# shd_v2_1.net
KiCad netlist of a schematic drawn in EAGLE
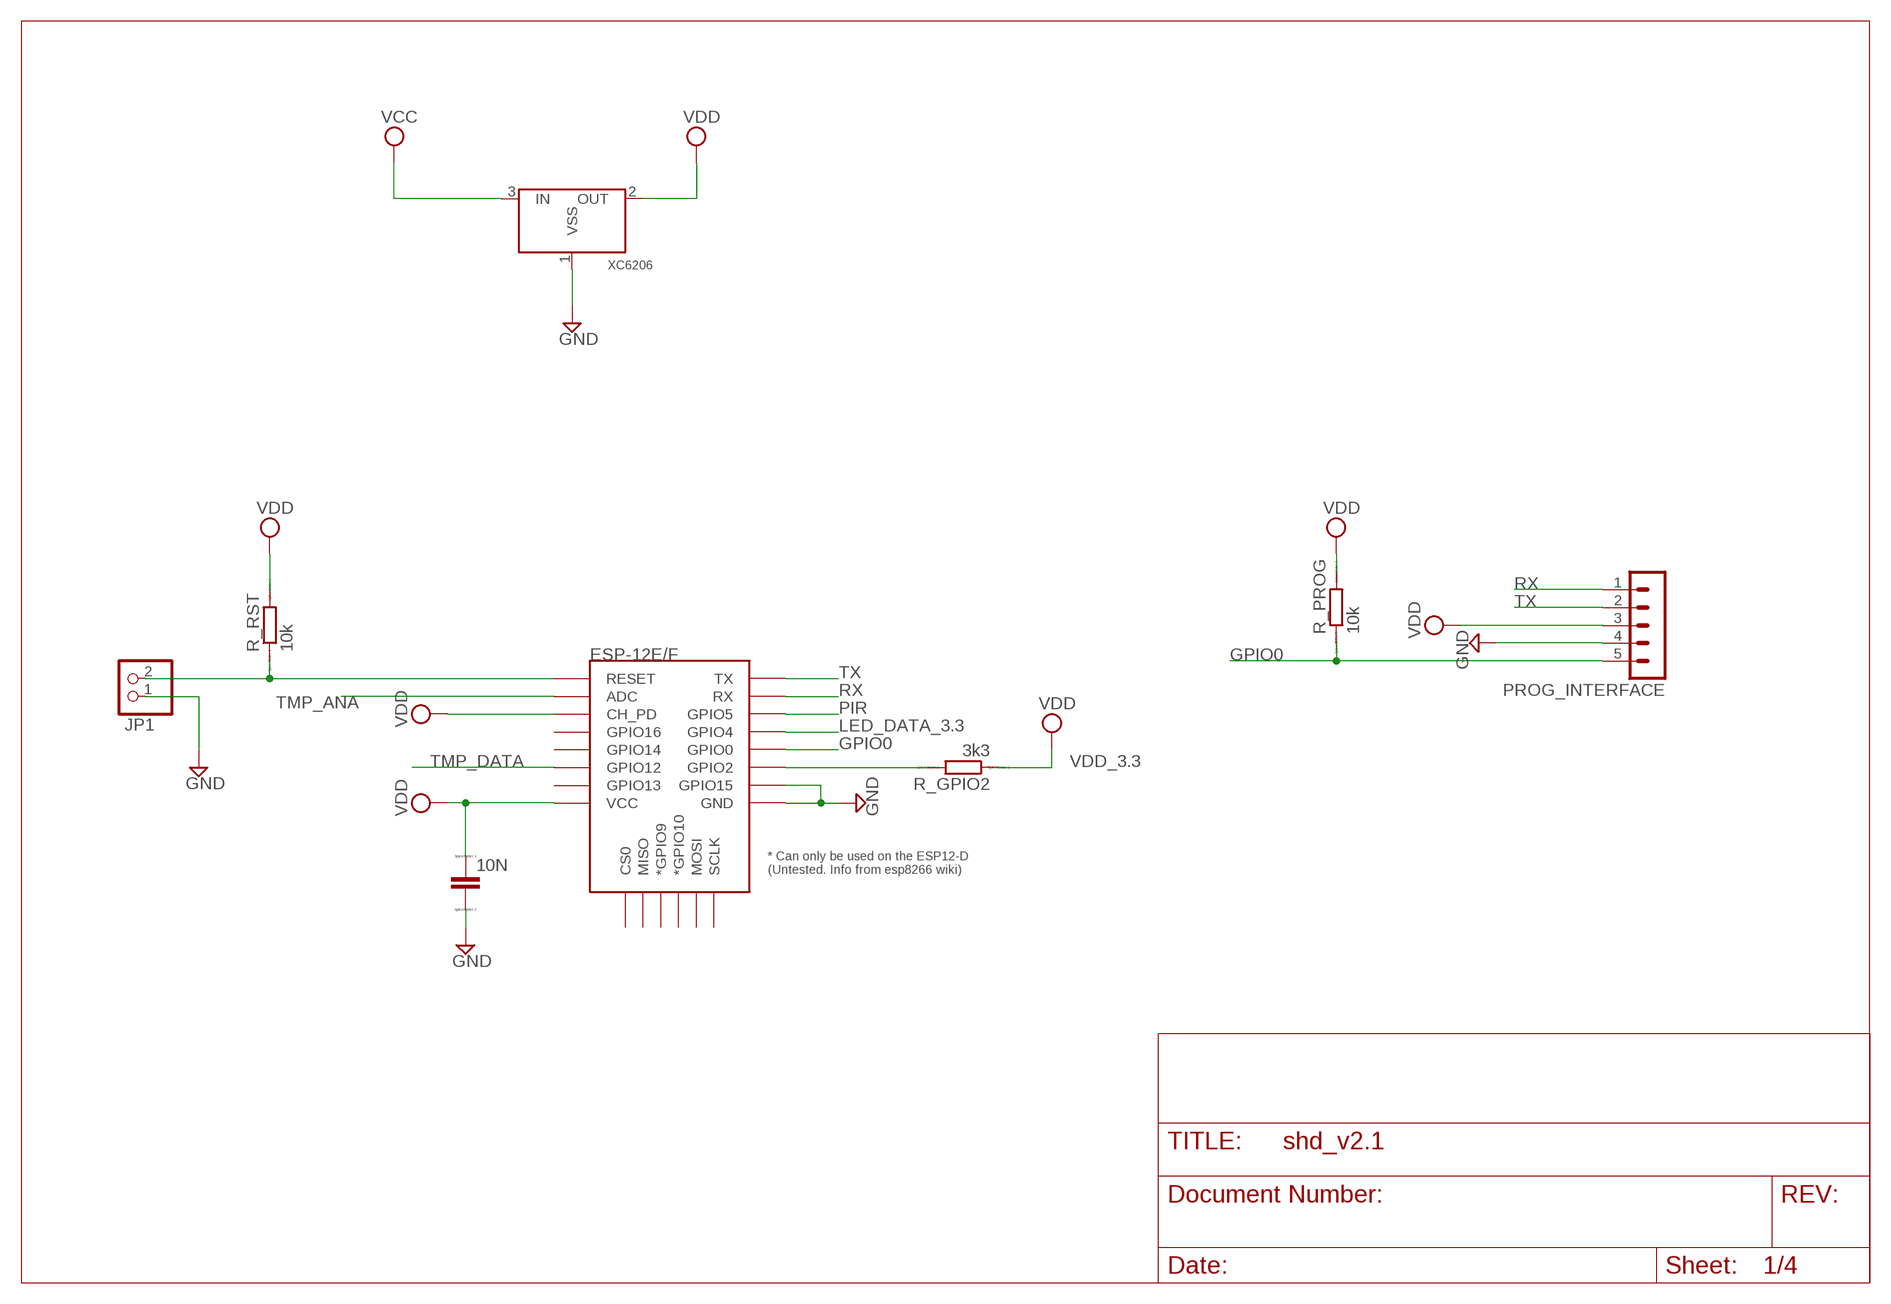
[diagram p0: schematic, sheet 1]
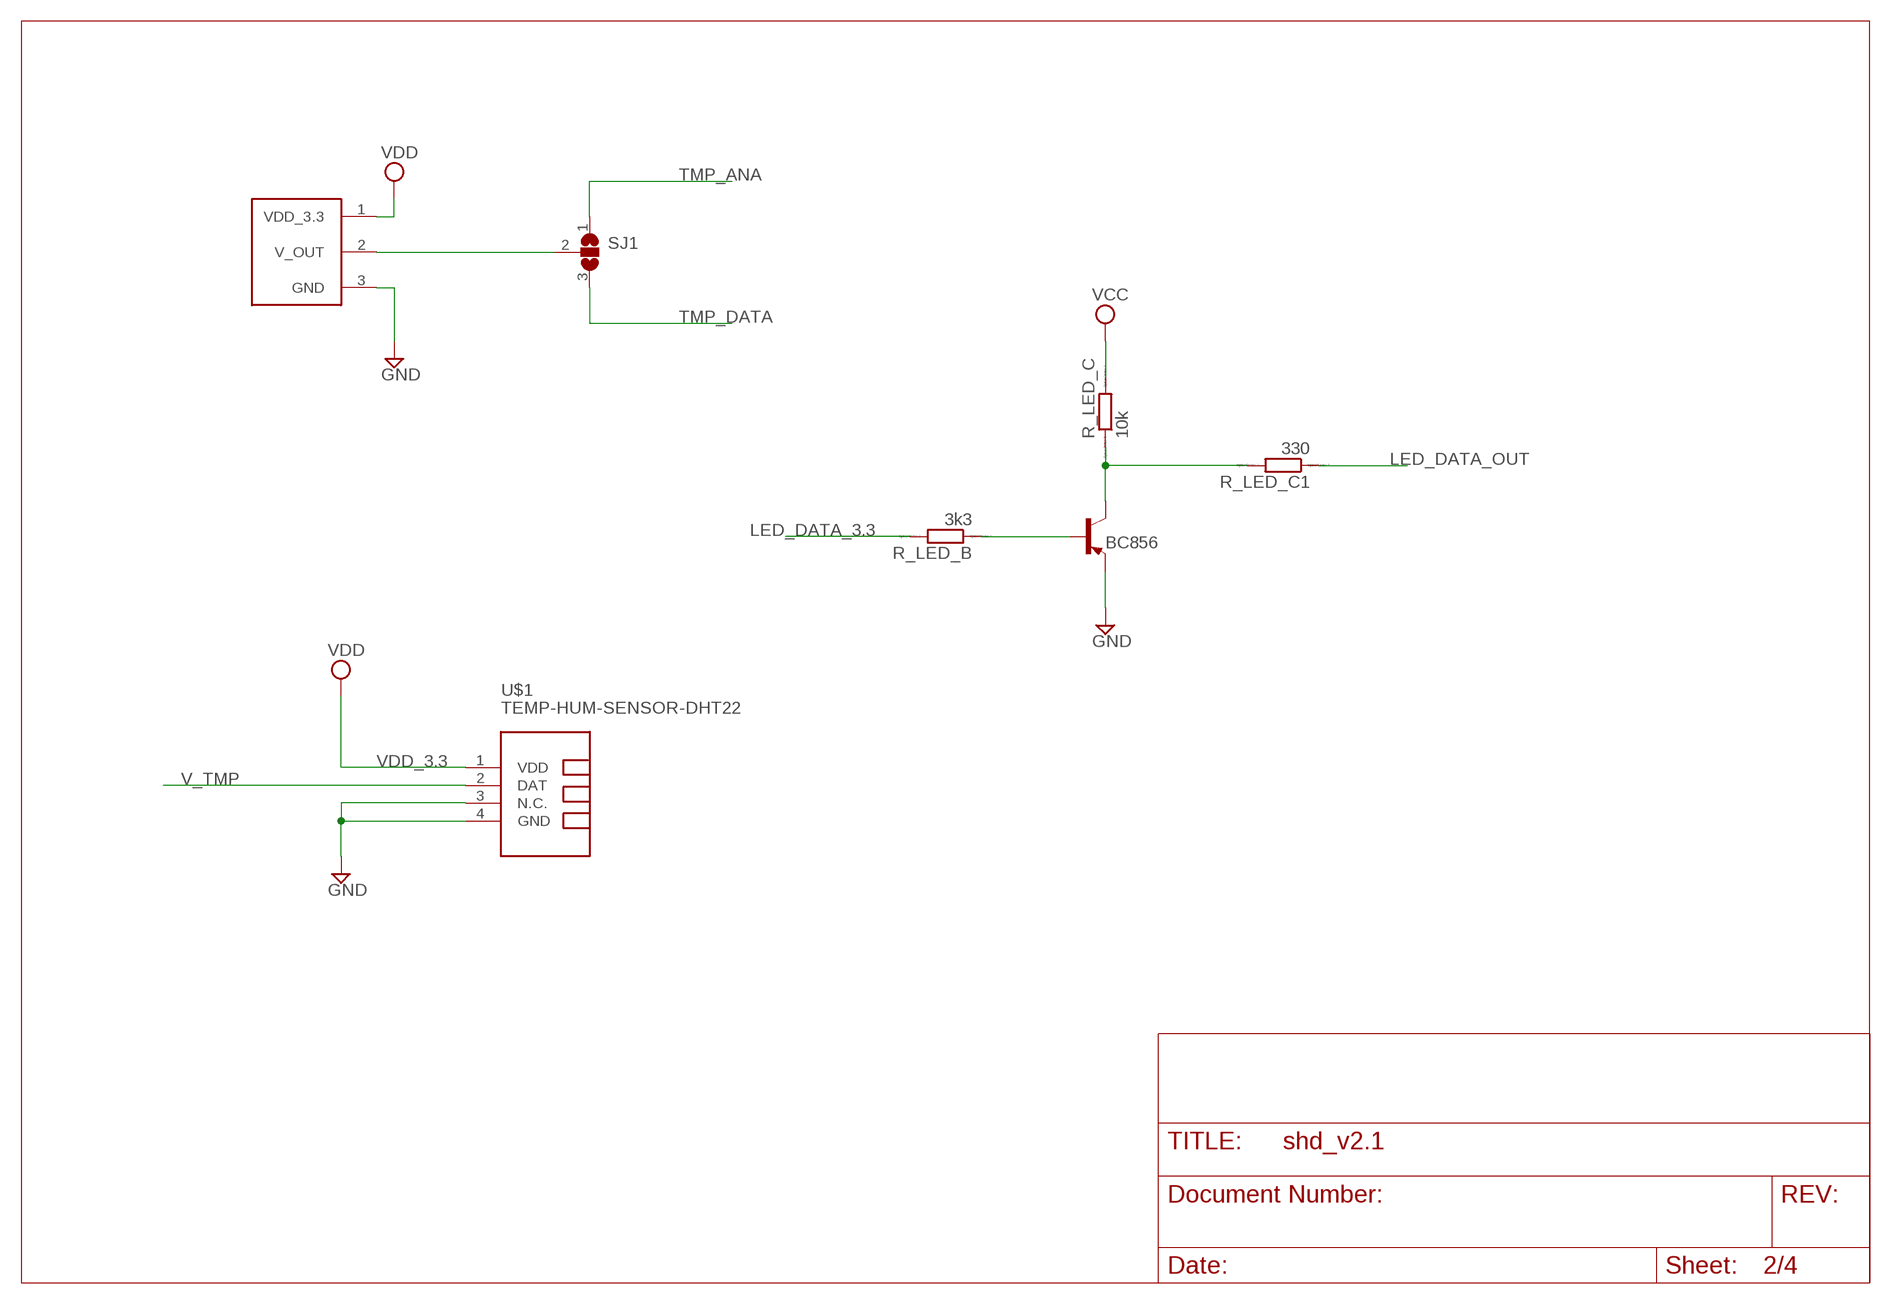
[diagram p1: schematic, sheet 2]
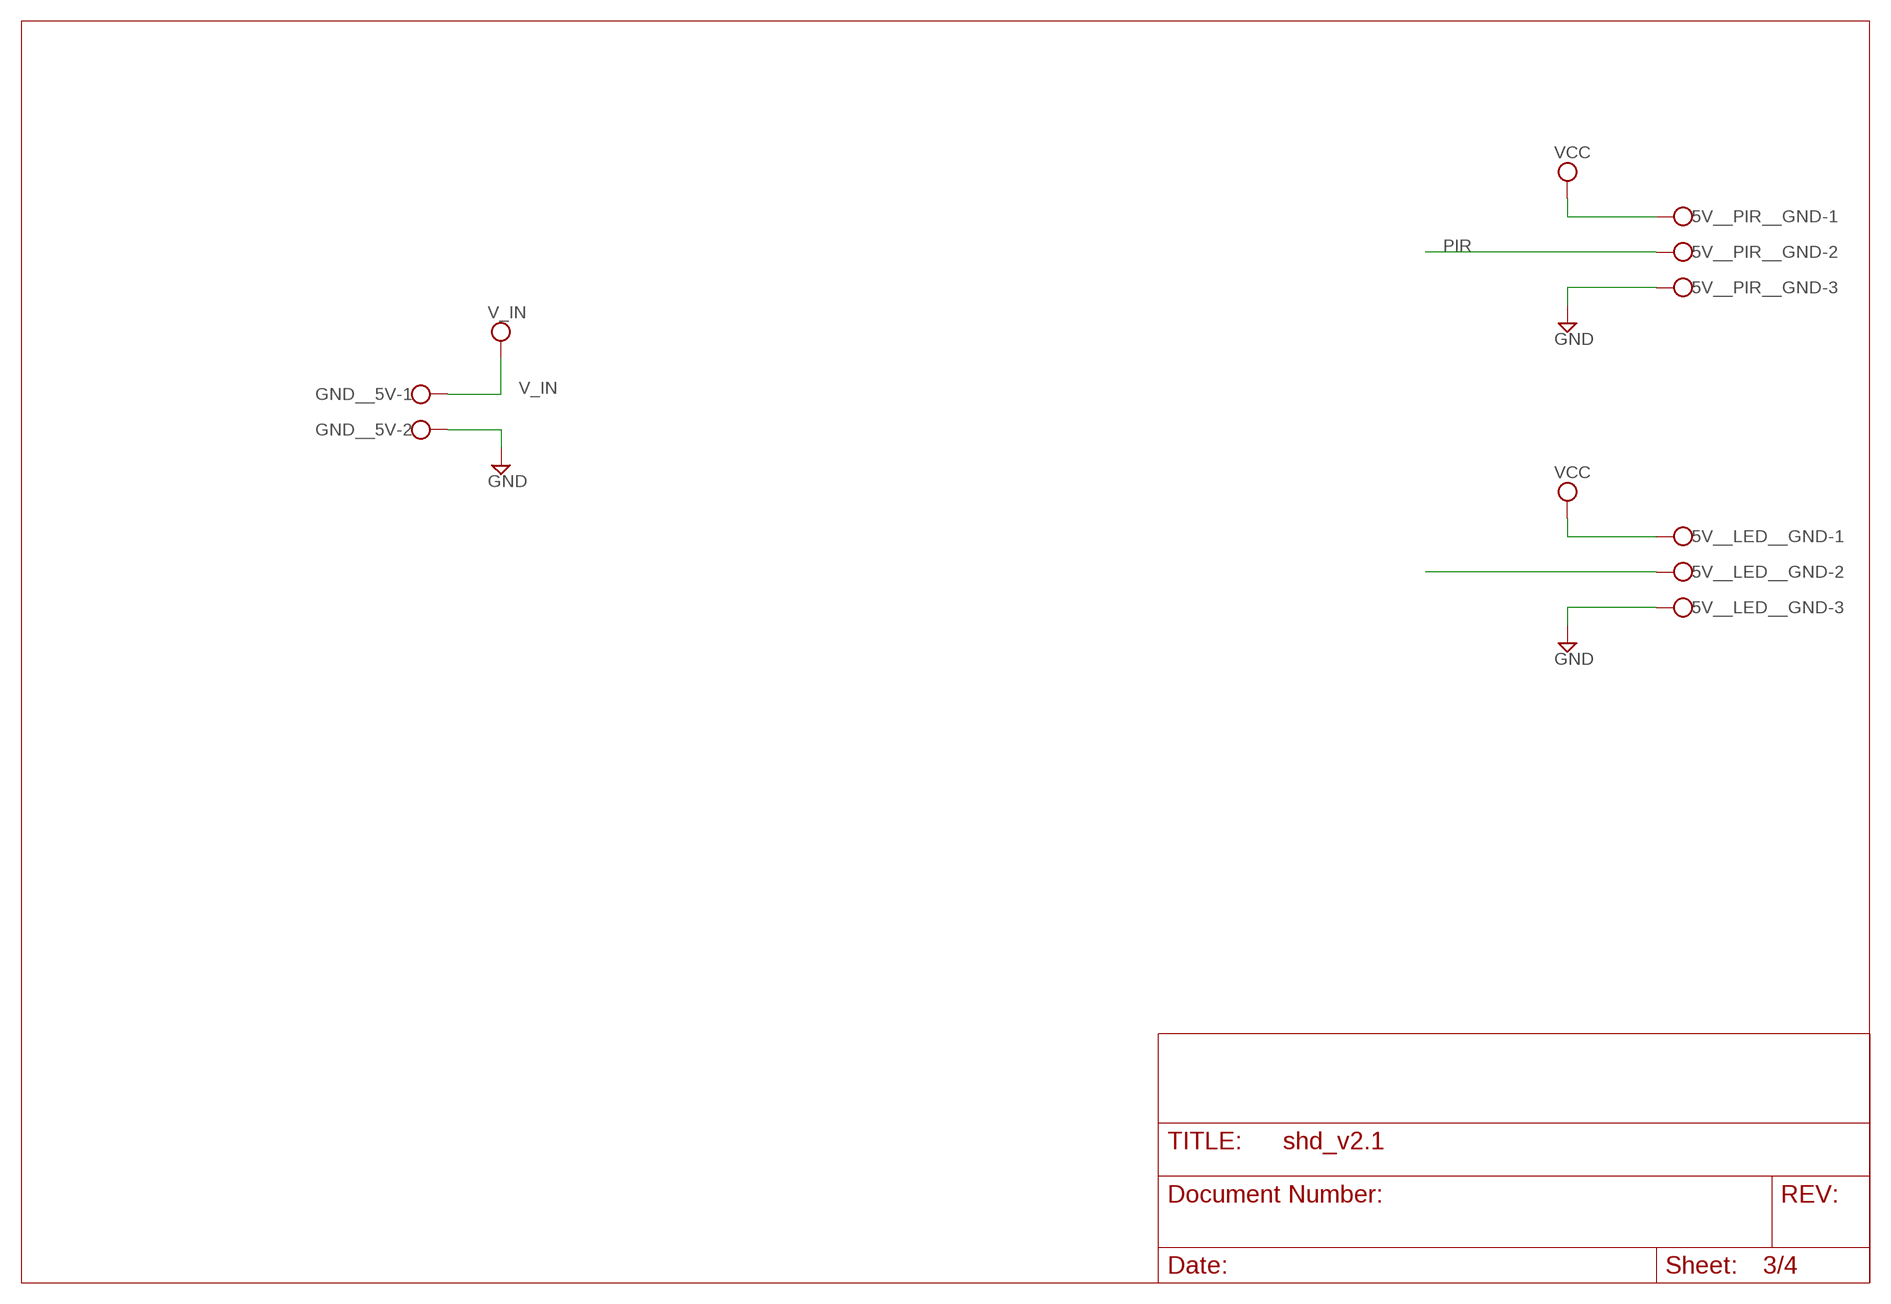
[diagram p2: schematic, sheet 3]
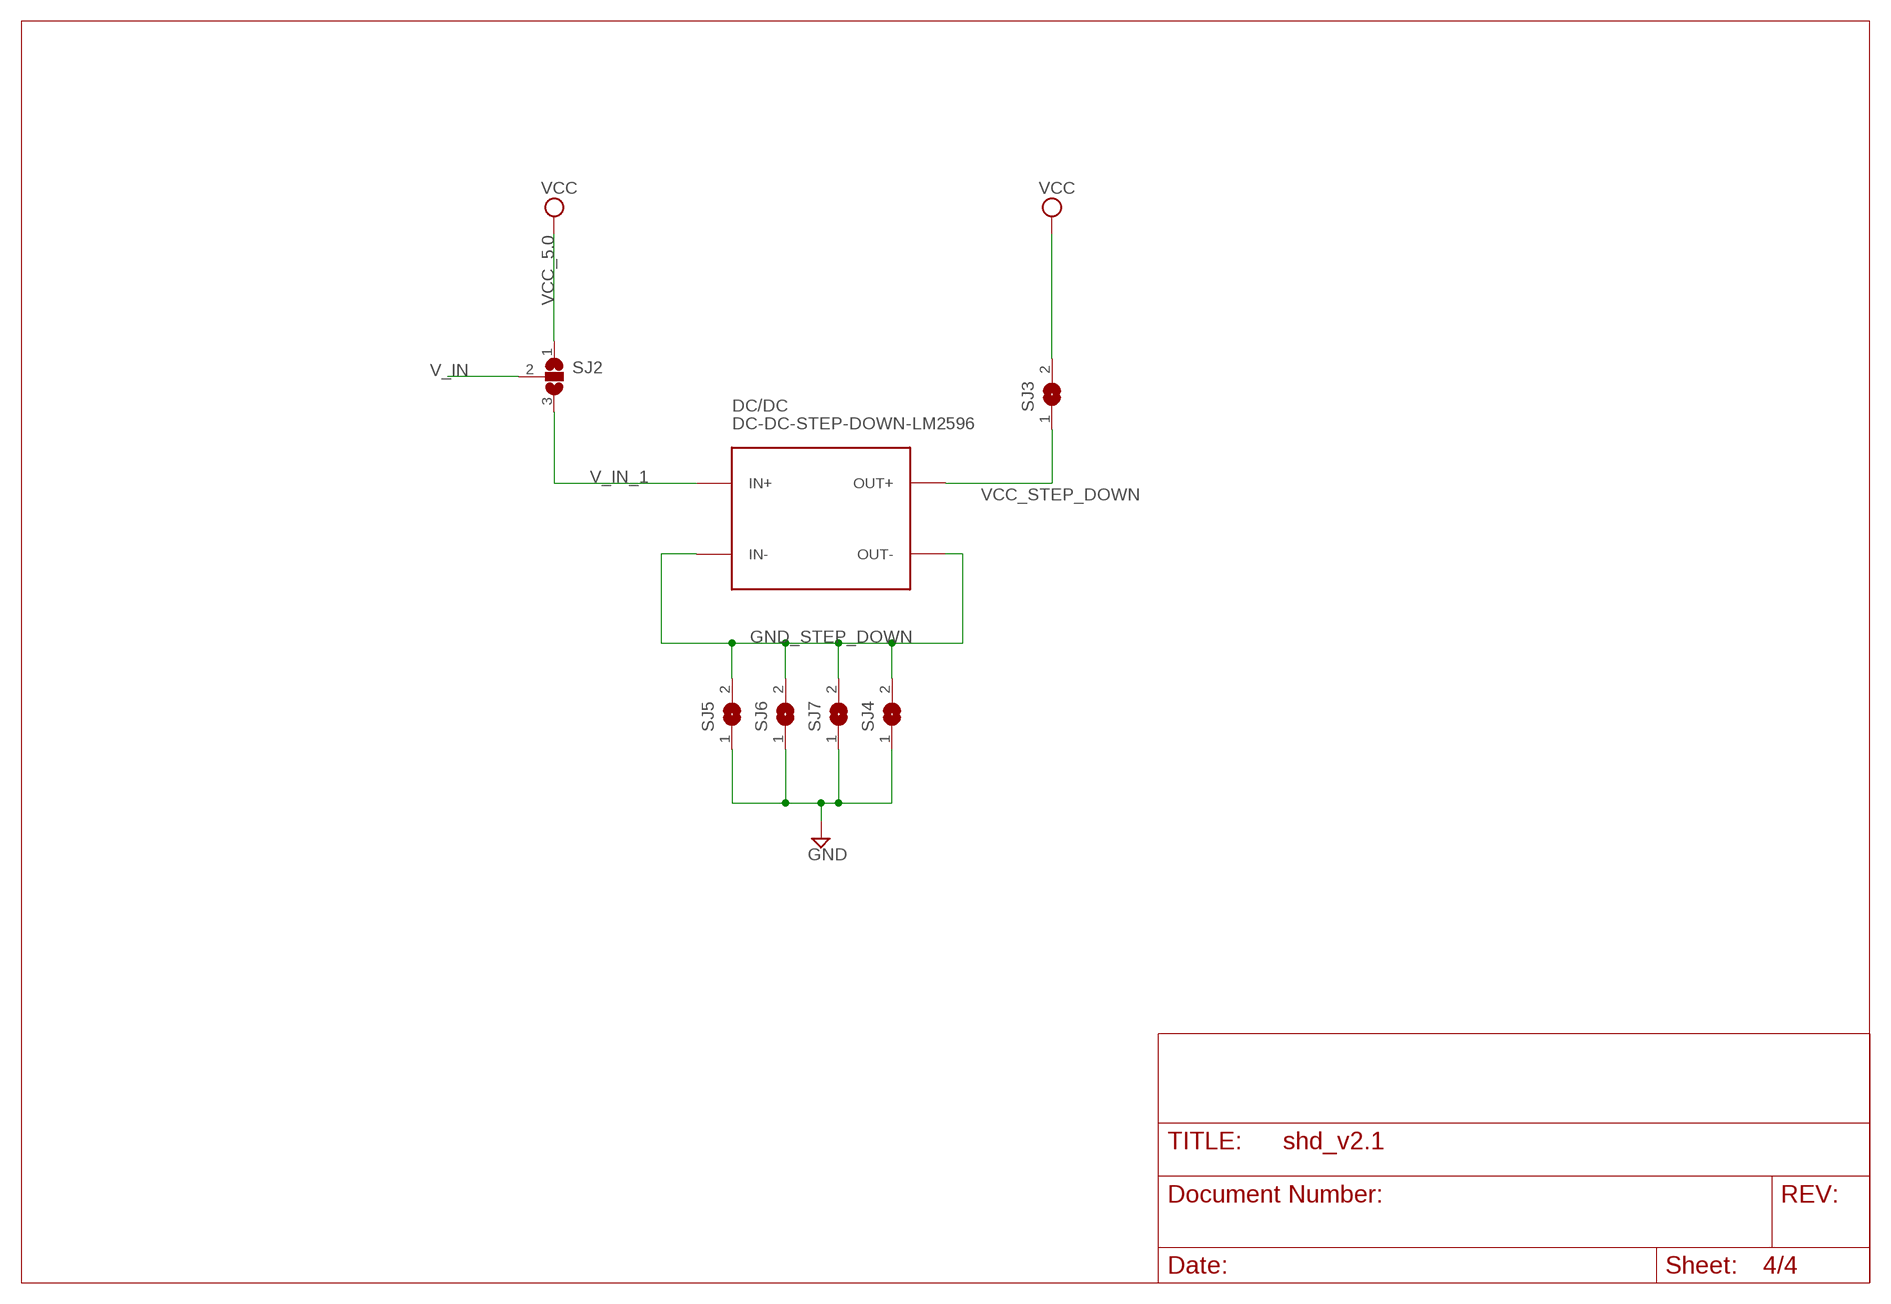
[diagram p3: schematic, sheet 4]

(export (version "E")
  (design (tool "Eeschema 10.0.6"))
  (components
    (comp (ref "DC/DC")
      (value "DC-DC-STEP-DOWN-LM2596")
      (footprint "eagle-import:DC-DC-STEP-DOWN-LM2596")
      (libsource (lib "eagle-import") (part "DC-DC-STEP-DOWN-LM2596"))
    )
    (comp (ref "SJ2")
      (value "SJ2W")
      (footprint "eagle-import:SJ_2")
      (libsource (lib "eagle-import") (part "SJ2W"))
    )
    (comp (ref "SJ3") (value "SJ") (footprint "eagle-import:SJ") (libsource (lib "eagle-import") (part "SJ")))
    (comp (ref "SJ4") (value "SJ") (footprint "eagle-import:SJ") (libsource (lib "eagle-import") (part "SJ")))
    (comp (ref "SJ5") (value "SJ") (footprint "eagle-import:SJ") (libsource (lib "eagle-import") (part "SJ")))
    (comp (ref "SJ6") (value "SJ") (footprint "eagle-import:SJ") (libsource (lib "eagle-import") (part "SJ")))
    (comp (ref "SJ7") (value "SJ") (footprint "eagle-import:SJ") (libsource (lib "eagle-import") (part "SJ")))
    (comp (ref "10N")
      (value "C")
      (footprint "eagle-import:C0805")
      (libsource (lib "eagle-import") (part "C"))
    )
    (comp (ref "ESP-12E/F")
      (value "ESP12ESMD")
      (footprint "eagle-import:ESP12E-SMD")
      (libsource (lib "eagle-import") (part "ESP12ESMD"))
    )
    (comp (ref "JP1")
      (value "PINHD-1X2")
      (footprint "eagle-import:1X02")
      (libsource (lib "eagle-import") (part "PINHD-1X2"))
    )
    (comp (ref "PROG_INTERFACE")
      (value "MA05-1")
      (footprint "eagle-import:MA05-1")
      (libsource (lib "eagle-import") (part "MA05-1"))
    )
    (comp (ref "R_GPIO2")
      (value "3k3")
      (footprint "eagle-import:0207_10")
      (libsource (lib "eagle-import") (part "R0207/10"))
    )
    (comp (ref "R_PROG")
      (value "10k")
      (footprint "eagle-import:0207_10")
      (libsource (lib "eagle-import") (part "R0207/10"))
    )
    (comp (ref "R_RST")
      (value "10k")
      (footprint "eagle-import:0207_10")
      (libsource (lib "eagle-import") (part "R0207/10"))
    )
    (comp (ref "XC6206")
      (value "XC6206")
      (footprint "eagle-import:SOT23")
      (libsource (lib "eagle-import") (part "XC6206"))
    )
    (comp (ref "BC856")
      (value "BC856A-PNP-SOT23-BEC")
      (footprint "eagle-import:SOT23-BEC")
      (libsource (lib "eagle-import") (part "-PNP-SOT23-BECBC856A"))
    )
    (comp (ref "R_LED_B")
      (value "3k3")
      (footprint "eagle-import:0207_10")
      (libsource (lib "eagle-import") (part "R0207/10"))
    )
    (comp (ref "R_LED_C")
      (value "10k")
      (footprint "eagle-import:0207_10")
      (libsource (lib "eagle-import") (part "R0207/10"))
    )
    (comp (ref "R_LED_C1")
      (value "330")
      (footprint "eagle-import:0207_10")
      (libsource (lib "eagle-import") (part "R0207/10"))
    )
    (comp (ref "SJ1")
      (value "SJ2W")
      (footprint "eagle-import:SJ_2")
      (libsource (lib "eagle-import") (part "SJ2W"))
    )
    (comp (ref "TMP")
      (value "TMP36")
      (footprint "eagle-import:TO-92")
      (libsource (lib "eagle-import") (part "TMP36"))
    )
    (comp (ref "U$1")
      (value "TEMP-HUM-SENSOR-DHT22")
      (footprint "eagle-import:TEMP-HUM-SENSOR-DHT22")
      (libsource (lib "eagle-import") (part "TEMP-HUM-SENSOR-DHT22"))
    )
    (comp (ref "5V__LED__GND")
      (value "W237-103")
      (footprint "eagle-import:W237-103")
      (fields (field (name "MPN") "237-103"))
      (libsource (lib "eagle-import") (part "W237-103"))
    )
    (comp (ref "5V__PIR__GND")
      (value "W237-103")
      (footprint "eagle-import:W237-103")
      (fields (field (name "MPN") "237-103"))
      (libsource (lib "eagle-import") (part "W237-103"))
    )
    (comp (ref "GND__5V")
      (value "W237-102")
      (footprint "eagle-import:W237-102")
      (fields (field (name "MPN") "237-102"))
      (libsource (lib "eagle-import") (part "W237-102"))
    )
  )
  (nets
    (net (code "1") (name "GND") (class "Default")
      (node (ref "10N") (pin "2") (pinfunction "2_2") (pintype "passive"))
      (node (ref "5V__LED__GND") (pin "3") (pinfunction "KL_3") (pintype "passive"))
      (node (ref "5V__PIR__GND") (pin "3") (pinfunction "KL_3") (pintype "passive"))
      (node (ref "BC856") (pin "E") (pinfunction "E_E") (pintype "passive"))
      (node (ref "ESP-12E/F") (pin "GND") (pinfunction "GND_GND") (pintype "bidirectional"))
      (node (ref "ESP-12E/F") (pin "GPIO15") (pinfunction "GPIO15_GPIO15") (pintype "bidirectional"))
      (node (ref "GND__5V") (pin "2") (pinfunction "KL_2") (pintype "passive"))
      (node (ref "JP1") (pin "1") (pinfunction "1_1") (pintype "passive"))
      (node (ref "PROG_INTERFACE") (pin "4") (pinfunction "4_4") (pintype "passive"))
      (node (ref "SJ4") (pin "1") (pinfunction "1_1") (pintype "passive"))
      (node (ref "SJ5") (pin "1") (pinfunction "1_1") (pintype "passive"))
      (node (ref "SJ6") (pin "1") (pinfunction "1_1") (pintype "passive"))
      (node (ref "SJ7") (pin "1") (pinfunction "1_1") (pintype "passive"))
      (node (ref "TMP") (pin "3") (pinfunction "GND_3") (pintype "power_in"))
      (node (ref "U$1") (pin "3") (pinfunction "N.C._3") (pintype "passive"))
      (node (ref "U$1") (pin "4") (pinfunction "GND_4") (pintype "power_in"))
      (node (ref "XC6206") (pin "1") (pinfunction "VSS_1") (pintype "bidirectional"))
    )
    (net (code "2") (name "GND_STEP_DOWN") (class "Default")
      (node (ref "DC/DC") (pin "IN-") (pinfunction "IN-_IN-") (pintype "bidirectional"))
      (node (ref "DC/DC") (pin "OUT-") (pinfunction "OUT-_OUT-") (pintype "bidirectional"))
      (node (ref "SJ4") (pin "2") (pinfunction "2_2") (pintype "passive"))
      (node (ref "SJ5") (pin "2") (pinfunction "2_2") (pintype "passive"))
      (node (ref "SJ6") (pin "2") (pinfunction "2_2") (pintype "passive"))
      (node (ref "SJ7") (pin "2") (pinfunction "2_2") (pintype "passive"))
    )
    (net (code "3") (name "GPIO0") (class "Default")
      (node (ref "ESP-12E/F") (pin "GPIO0") (pinfunction "GPIO0_GPIO0") (pintype "bidirectional"))
      (node (ref "PROG_INTERFACE") (pin "5") (pinfunction "5_5") (pintype "passive"))
      (node (ref "R_PROG") (pin "1") (pinfunction "1_1") (pintype "passive"))
    )
    (net (code "4") (name "LED_DATA_3.3") (class "Default")
      (node (ref "ESP-12E/F") (pin "GPIO4") (pinfunction "GPIO4_GPIO4") (pintype "bidirectional"))
      (node (ref "R_LED_B") (pin "2") (pinfunction "2_2") (pintype "passive"))
    )
    (net (code "5") (name "LED_DATA_OUT") (class "Default")
      (node (ref "5V__LED__GND") (pin "2") (pinfunction "KL_2") (pintype "passive"))
      (node (ref "R_LED_C1") (pin "1") (pinfunction "1_1") (pintype "passive"))
    )
    (net (code "6") (name "Net-(BC856-PadB)") (class "Default")
      (node (ref "BC856") (pin "B") (pinfunction "B_B") (pintype "passive"))
      (node (ref "R_LED_B") (pin "1") (pinfunction "1_1") (pintype "passive"))
    )
    (net (code "7") (name "Net-(BC856-PadC)") (class "Default")
      (node (ref "BC856") (pin "C") (pinfunction "C_C") (pintype "passive"))
      (node (ref "R_LED_C") (pin "1") (pinfunction "1_1") (pintype "passive"))
      (node (ref "R_LED_C1") (pin "2") (pinfunction "2_2") (pintype "passive"))
    )
    (net (code "8") (name "Net-(ESP-12E/F-PadGPIO2)") (class "Default")
      (node (ref "ESP-12E/F") (pin "GPIO2") (pinfunction "GPIO2_GPIO2") (pintype "bidirectional"))
      (node (ref "R_GPIO2") (pin "2") (pinfunction "2_2") (pintype "passive"))
    )
    (net (code "9") (name "Net-(ESP-12E/F-PadRESET)") (class "Default")
      (node (ref "ESP-12E/F") (pin "RESET") (pinfunction "RESET_RESET") (pintype "bidirectional"))
      (node (ref "JP1") (pin "2") (pinfunction "2_2") (pintype "passive"))
      (node (ref "R_RST") (pin "1") (pinfunction "1_1") (pintype "passive"))
    )
    (net (code "10") (name "PIR") (class "Default")
      (node (ref "5V__PIR__GND") (pin "2") (pinfunction "KL_2") (pintype "passive"))
      (node (ref "ESP-12E/F") (pin "GPIO5") (pinfunction "GPIO5_GPIO5") (pintype "bidirectional"))
    )
    (net (code "11") (name "RX") (class "Default")
      (node (ref "ESP-12E/F") (pin "RXD0") (pinfunction "RX_RXD0") (pintype "bidirectional"))
      (node (ref "PROG_INTERFACE") (pin "1") (pinfunction "1_1") (pintype "passive"))
    )
    (net (code "12") (name "TMP_ANA") (class "Default")
      (node (ref "ESP-12E/F") (pin "ADC") (pinfunction "ADC_ADC") (pintype "bidirectional"))
      (node (ref "SJ1") (pin "1") (pinfunction "1_1") (pintype "passive"))
    )
    (net (code "13") (name "TMP_DATA") (class "Default")
      (node (ref "ESP-12E/F") (pin "GPIO12") (pinfunction "GPIO12_GPIO12") (pintype "bidirectional"))
      (node (ref "SJ1") (pin "3") (pinfunction "3_3") (pintype "passive"))
    )
    (net (code "14") (name "TX") (class "Default")
      (node (ref "ESP-12E/F") (pin "TXD0") (pinfunction "TX_TXD0") (pintype "bidirectional"))
      (node (ref "PROG_INTERFACE") (pin "2") (pinfunction "2_2") (pintype "passive"))
    )
    (net (code "15") (name "VCC_5.0") (class "Default")
      (node (ref "5V__LED__GND") (pin "1") (pinfunction "KL_1") (pintype "passive"))
      (node (ref "5V__PIR__GND") (pin "1") (pinfunction "KL_1") (pintype "passive"))
      (node (ref "R_LED_C") (pin "2") (pinfunction "2_2") (pintype "passive"))
      (node (ref "SJ2") (pin "1") (pinfunction "1_1") (pintype "passive"))
      (node (ref "SJ3") (pin "2") (pinfunction "2_2") (pintype "passive"))
      (node (ref "XC6206") (pin "3") (pinfunction "IN_3") (pintype "bidirectional"))
    )
    (net (code "16") (name "VCC_STEP_DOWN") (class "Default")
      (node (ref "DC/DC") (pin "OUT+") (pinfunction "OUT+_OUT+") (pintype "bidirectional"))
      (node (ref "SJ3") (pin "1") (pinfunction "1_1") (pintype "passive"))
    )
    (net (code "17") (name "VDD_3.3") (class "Default")
      (node (ref "10N") (pin "1") (pinfunction "1_1") (pintype "passive"))
      (node (ref "ESP-12E/F") (pin "CH_PD") (pinfunction "CH_PD_CH_PD") (pintype "bidirectional"))
      (node (ref "ESP-12E/F") (pin "VCC") (pinfunction "VCC_VCC") (pintype "bidirectional"))
      (node (ref "PROG_INTERFACE") (pin "3") (pinfunction "3_3") (pintype "passive"))
      (node (ref "R_GPIO2") (pin "1") (pinfunction "1_1") (pintype "passive"))
      (node (ref "R_PROG") (pin "2") (pinfunction "2_2") (pintype "passive"))
      (node (ref "R_RST") (pin "2") (pinfunction "2_2") (pintype "passive"))
      (node (ref "TMP") (pin "1") (pinfunction "VDD_3.3_1") (pintype "power_in"))
      (node (ref "U$1") (pin "1") (pinfunction "VDD_1") (pintype "power_in"))
      (node (ref "XC6206") (pin "2") (pinfunction "OUT_2") (pintype "bidirectional"))
    )
    (net (code "18") (name "V_IN") (class "Default")
      (node (ref "GND__5V") (pin "1") (pinfunction "KL_1") (pintype "passive"))
      (node (ref "SJ2") (pin "2") (pinfunction "2_2") (pintype "passive"))
    )
    (net (code "19") (name "V_IN_1") (class "Default")
      (node (ref "DC/DC") (pin "IN+") (pinfunction "IN+_IN+") (pintype "bidirectional"))
      (node (ref "SJ2") (pin "3") (pinfunction "3_3") (pintype "passive"))
    )
    (net (code "20") (name "V_TMP") (class "Default")
      (node (ref "SJ1") (pin "2") (pinfunction "2_2") (pintype "passive"))
      (node (ref "TMP") (pin "2") (pinfunction "V_OUT_2") (pintype "output"))
      (node (ref "U$1") (pin "2") (pinfunction "DAT_2") (pintype "bidirectional"))
    )
    (net (code "21") (name "unconnected-(ESP-12E/F-*GPIO9-PadGPIO9)") (class "Default")
      (node (ref "ESP-12E/F") (pin "GPIO9") (pinfunction "*GPIO9_GPIO9") (pintype "bidirectional"))
    )
    (net (code "22") (name "unconnected-(ESP-12E/F-*GPIO10-PadGPIO10)") (class "Default")
      (node (ref "ESP-12E/F") (pin "GPIO10") (pinfunction "*GPIO10_GPIO10") (pintype "bidirectional"))
    )
    (net (code "23") (name "unconnected-(ESP-12E/F-PadCS0)") (class "Default")
      (node (ref "ESP-12E/F") (pin "CS0") (pinfunction "CS0_CS0") (pintype "bidirectional"))
    )
    (net (code "24") (name "unconnected-(ESP-12E/F-PadGPIO13)") (class "Default")
      (node (ref "ESP-12E/F") (pin "GPIO13") (pinfunction "GPIO13_GPIO13") (pintype "bidirectional"))
    )
    (net (code "25") (name "unconnected-(ESP-12E/F-PadGPIO14)") (class "Default")
      (node (ref "ESP-12E/F") (pin "GPIO14") (pinfunction "GPIO14_GPIO14") (pintype "bidirectional"))
    )
    (net (code "26") (name "unconnected-(ESP-12E/F-PadGPIO16)") (class "Default")
      (node (ref "ESP-12E/F") (pin "GPIO16") (pinfunction "GPIO16_GPIO16") (pintype "bidirectional"))
    )
    (net (code "27") (name "unconnected-(ESP-12E/F-PadMISO)") (class "Default")
      (node (ref "ESP-12E/F") (pin "MISO") (pinfunction "MISO_MISO") (pintype "bidirectional"))
    )
    (net (code "28") (name "unconnected-(ESP-12E/F-PadMOSI)") (class "Default")
      (node (ref "ESP-12E/F") (pin "MOSI") (pinfunction "MOSI_MOSI") (pintype "bidirectional"))
    )
    (net (code "29") (name "unconnected-(ESP-12E/F-PadSCLK)") (class "Default")
      (node (ref "ESP-12E/F") (pin "SCLK") (pinfunction "SCLK_SCLK") (pintype "bidirectional"))
    )
  )
)
